# Power.net
KiCad netlist of a schematic drawn in Altium Designer
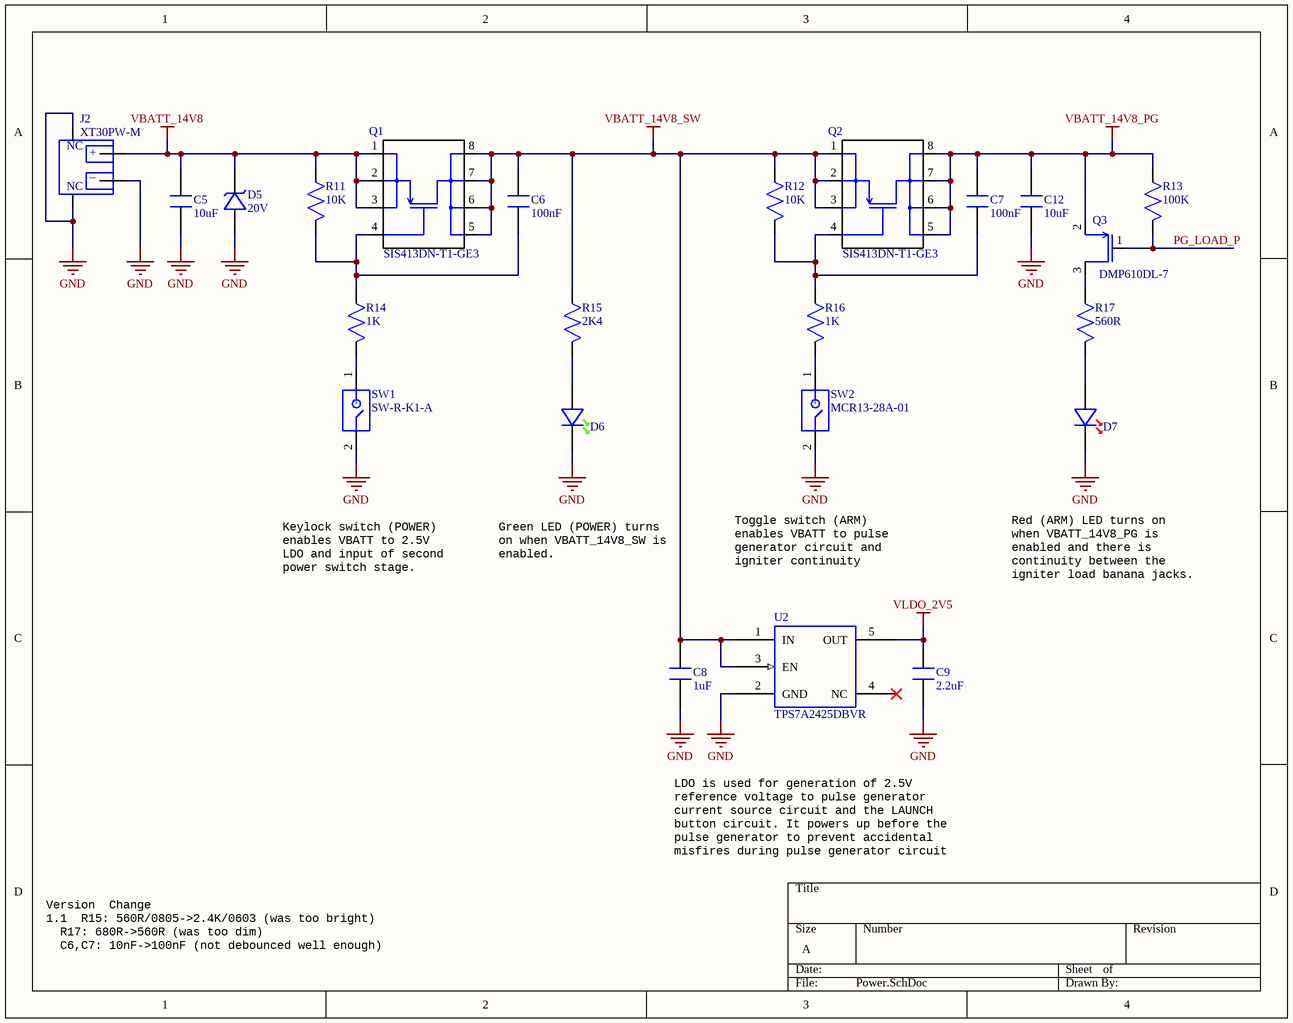
[diagram p0: Power.SchDoc]

(export (version "E")
  (design (tool "Eeschema 10.0.6"))
  (components
    (comp (ref "C5")
      (value "~")
      (footprint "1206_CAP")
      (fields
        (field (name "MANUFACTURER") "Samsung Electro-Mechanics")
        (field (name "PART NUMBER") "CL31A106MBHNNNE")
        (field (name "TOLERANCE") "20%")
        (field (name "CAPACITANCE") "10uF")
      )
      (libsource (lib "SharedPartsLib") (part "CAP_1206_10uF"))
    )
    (comp (ref "C6")
      (value "CAP_0603_100nF")
      (footprint "0603_CAP")
      (fields
        (field (name "MANUFACTURER") "Samsung Electro-Mechanics")
        (field (name "PART NUMBER") "CL10B104KB8NNWC")
        (field (name "TOLERANCE") "10%")
        (field (name "CAPACITANCE") "100nF")
      )
      (libsource (lib "SharedPartsLib") (part "CAP_0603_100nF"))
    )
    (comp (ref "C7")
      (value "CAP_0603_100nF")
      (footprint "0603_CAP")
      (fields
        (field (name "MANUFACTURER") "Samsung Electro-Mechanics")
        (field (name "PART NUMBER") "CL10B104KB8NNWC")
        (field (name "TOLERANCE") "10%")
        (field (name "CAPACITANCE") "100nF")
      )
      (libsource (lib "SharedPartsLib") (part "CAP_0603_100nF"))
    )
    (comp (ref "C8")
      (value "~")
      (footprint "0603_CAP")
      (fields
        (field (name "MANUFACTURER") "Samsung Electro-Mechanics")
        (field (name "PART NUMBER") "CL10B105KA8NNNC")
        (field (name "TOLERANCE") "10%")
        (field (name "CAPACITANCE") "1uF")
      )
      (libsource (lib "SharedPartsLib") (part "CAP_0603_1uF"))
    )
    (comp (ref "C9")
      (value "~")
      (footprint "0603_CAP")
      (fields
        (field (name "MANUFACTURER") "Samsung Electro-Mechanics")
        (field (name "PART NUMBER") "CL10B225KP8NNNC")
        (field (name "TOLERANCE") "10%")
        (field (name "CAPACITANCE") "2.2uF")
      )
      (libsource (lib "SharedPartsLib") (part "CAP_0603_2.2uF"))
    )
    (comp (ref "C12")
      (value "~")
      (footprint "1206_CAP")
      (fields
        (field (name "MANUFACTURER") "Samsung Electro-Mechanics")
        (field (name "PART NUMBER") "CL31A106MBHNNNE")
        (field (name "TOLERANCE") "20%")
        (field (name "CAPACITANCE") "10uF")
      )
      (libsource (lib "SharedPartsLib") (part "CAP_1206_10uF"))
    )
    (comp (ref "D5")
      (value "*")
      (footprint "DO-214AC_SMA")
      (fields
        (field (name "MANUFACTURER") "Diodes Incorporated")
        (field (name "PART NUMBER") "SMAJ20AQ-13-F")
        (field (name "REVERSE STANDOFF VOLTAGE") "20V")
      )
      (libsource (lib "SharedPartsLib") (part "DIODE_TVS_20V_UNIDIR"))
    )
    (comp (ref "D6")
      (value "*")
      (footprint "LED_1411")
      (fields (field (name "MANUFACTURER") "Würth Elektronik") (field (name "PART NUMBER") "150141GS73100"))
      (libsource (lib "SharedPartsLib") (part "LED_GREEN_150141GS73100"))
    )
    (comp (ref "D7")
      (value "*")
      (footprint "LED_1411")
      (fields (field (name "MANUFACTURER") "Würth Elektronik") (field (name "PART NUMBER") "150141RS73100"))
      (libsource (lib "SharedPartsLib") (part "LED_RED_150141RS73100"))
    )
    (comp (ref "J2")
      (value "~")
      (footprint "CONN_PLUG_XT30PW-M")
      (fields (field (name "MANUFACTURER") "AMASS") (field (name "PART NUMBER") "XT30PW-M"))
      (libsource (lib "SharedPartsLib") (part "CONN_PLUG_XT30PW-M"))
    )
    (comp (ref "Q1")
      (value "*")
      (footprint "PFET_POWERPAK_1212-8")
      (fields (field (name "MANUFACTURER") "Vishay Siliconix") (field (name "PART NUMBER") "SIS413DN-T1-GE3"))
      (libsource (lib "SharedPartsLib") (part "PFET_SIS413DN"))
    )
    (comp (ref "Q2")
      (value "*")
      (footprint "PFET_POWERPAK_1212-8")
      (fields (field (name "MANUFACTURER") "Vishay Siliconix") (field (name "PART NUMBER") "SIS413DN-T1-GE3"))
      (libsource (lib "SharedPartsLib") (part "PFET_SIS413DN"))
    )
    (comp (ref "Q3")
      (value "*")
      (footprint "SOT-23-3")
      (fields (field (name "MANUFACTURER") "Diodes Incorporated") (field (name "PART NUMBER") "DMP610DL-7"))
      (libsource (lib "SharedPartsLib") (part "PFET_DMP610DL"))
    )
    (comp (ref "R11")
      (value "~")
      (footprint "0603_RES")
      (fields
        (field (name "MANUFACTURER") "Stackpole Electronics Inc")
        (field (name "PART NUMBER") "RMCF0603FT10K0")
        (field (name "TOLERANCE") "1%")
        (field (name "RESISTANCE") "10K")
      )
      (libsource (lib "SharedPartsLib") (part "RES_0603_10K"))
    )
    (comp (ref "R12")
      (value "~")
      (footprint "0603_RES")
      (fields
        (field (name "MANUFACTURER") "Stackpole Electronics Inc")
        (field (name "PART NUMBER") "RMCF0603FT10K0")
        (field (name "TOLERANCE") "1%")
        (field (name "RESISTANCE") "10K")
      )
      (libsource (lib "SharedPartsLib") (part "RES_0603_10K"))
    )
    (comp (ref "R13")
      (value "~")
      (footprint "0603_RES")
      (fields
        (field (name "MANUFACTURER") "Stackpole")
        (field (name "PART NUMBER") "RMCF0603FT100K")
        (field (name "TOLERANCE") "1%")
        (field (name "RESISTANCE") "100K")
      )
      (libsource (lib "SharedPartsLib") (part "RES_0603_100K"))
    )
    (comp (ref "R14")
      (value "~")
      (footprint "0603_RES")
      (fields
        (field (name "MANUFACTURER") "Stackpole Electronics Inc")
        (field (name "PART NUMBER") "RMCF0603FT1K00")
        (field (name "TOLERANCE") "1%")
        (field (name "RESISTANCE") "1K")
      )
      (libsource (lib "SharedPartsLib") (part "RES_0603_1K"))
    )
    (comp (ref "R15")
      (value "RES_0603_2K4")
      (footprint "0603_RES")
      (fields
        (field (name "MANUFACTURER") "Stackpole Electronics Inc")
        (field (name "PART NUMBER") "RMCF0603FT2K40")
        (field (name "TOLERANCE") "1%")
        (field (name "RESISTANCE") "2K4")
      )
      (libsource (lib "SharedPartsLib") (part "RES_0603_2K4"))
    )
    (comp (ref "R16")
      (value "~")
      (footprint "0603_RES")
      (fields
        (field (name "MANUFACTURER") "Stackpole Electronics Inc")
        (field (name "PART NUMBER") "RMCF0603FT1K00")
        (field (name "TOLERANCE") "1%")
        (field (name "RESISTANCE") "1K")
      )
      (libsource (lib "SharedPartsLib") (part "RES_0603_1K"))
    )
    (comp (ref "R17")
      (value "RES_0805_560R")
      (footprint "0805_RES")
      (fields
        (field (name "MANUFACTURER") "Vishay Dale")
        (field (name "PART NUMBER") "CRCW0805560RFKEAHP")
        (field (name "TOLERANCE") "1%")
        (field (name "RESISTANCE") "560R")
      )
      (libsource (lib "SharedPartsLib") (part "RES_0805_560R"))
    )
    (comp (ref "SW1")
      (value "*")
      (footprint "SW_KEYLOCK_SW-R-K1-A")
      (fields (field (name "MANUFACTURER") "Adam Tech") (field (name "PART NUMBER") "SW-R-K1-A"))
      (libsource (lib "SharedPartsLib") (part "SW_KEYLOCK_SW-R-K1-A"))
    )
    (comp (ref "SW2")
      (value "*")
      (footprint "SW_TOGGLE_MCR13-28A-01")
      (fields (field (name "MANUFACTURER") "Multicomp") (field (name "PART NUMBER") "MCR13-28A-01"))
      (libsource (lib "SharedPartsLib") (part "SW_TOGGLE_MCR13-28A-01"))
    )
    (comp (ref "U2")
      (value "TPS7A2425DBVR")
      (footprint "SOT-23-5")
      (fields (field (name "MANUFACTURER") "Texas Instruments") (field (name "PART NUMBER") "TPS7A2425DBVR"))
      (libsource (lib "SharedPartsLib") (part "TPS7A2425DBVR"))
    )
  )
  (nets
    (net (code "1") (name "/PG_LOAD_P") (class "Default")
      (node (ref "Q3") (pin "1") (pinfunction "G_1") (pintype "passive"))
      (node (ref "R13") (pin "1") (pintype "passive"))
    )
    (net (code "2") (name "GND") (class "Default")
      (node (ref "C12") (pin "1") (pintype "passive"))
      (node (ref "C5") (pin "1") (pintype "passive"))
      (node (ref "C8") (pin "1") (pintype "passive"))
      (node (ref "C9") (pin "1") (pintype "passive"))
      (node (ref "D5") (pin "2") (pintype "passive"))
      (node (ref "D6") (pin "1") (pintype "passive"))
      (node (ref "D7") (pin "1") (pintype "passive"))
      (node (ref "J2") (pin "2") (pintype "passive"))
      (node (ref "SW1") (pin "2") (pintype "passive"))
      (node (ref "SW2") (pin "2") (pintype "passive"))
      (node (ref "U2") (pin "2") (pinfunction "GND_2") (pintype "passive"))
    )
    (net (code "3") (name "Net-(D6-Pad2)") (class "Default")
      (node (ref "D6") (pin "2") (pintype "passive"))
      (node (ref "R15") (pin "1") (pintype "passive"))
    )
    (net (code "4") (name "Net-(D7-Pad2)") (class "Default")
      (node (ref "D7") (pin "2") (pintype "passive"))
      (node (ref "R17") (pin "1") (pintype "passive"))
    )
    (net (code "5") (name "Net-(Q1-G)") (class "Default")
      (node (ref "C6") (pin "1") (pintype "passive"))
      (node (ref "Q1") (pin "4") (pinfunction "G_4") (pintype "passive"))
      (node (ref "R11") (pin "1") (pintype "passive"))
      (node (ref "R14") (pin "2") (pintype "passive"))
    )
    (net (code "6") (name "Net-(Q2-G)") (class "Default")
      (node (ref "C7") (pin "1") (pintype "passive"))
      (node (ref "Q2") (pin "4") (pinfunction "G_4") (pintype "passive"))
      (node (ref "R12") (pin "1") (pintype "passive"))
      (node (ref "R16") (pin "2") (pintype "passive"))
    )
    (net (code "7") (name "Net-(Q3-D)") (class "Default")
      (node (ref "Q3") (pin "3") (pinfunction "D_3") (pintype "passive"))
      (node (ref "R17") (pin "2") (pintype "passive"))
    )
    (net (code "8") (name "Net-(R14-Pad1)") (class "Default")
      (node (ref "R14") (pin "1") (pintype "passive"))
      (node (ref "SW1") (pin "1") (pintype "passive"))
    )
    (net (code "9") (name "Net-(R16-Pad1)") (class "Default")
      (node (ref "R16") (pin "1") (pintype "passive"))
      (node (ref "SW2") (pin "1") (pintype "passive"))
    )
    (net (code "10") (name "VBATT_14V8") (class "Default")
      (node (ref "C5") (pin "2") (pintype "passive"))
      (node (ref "D5") (pin "1") (pintype "passive"))
      (node (ref "J2") (pin "1") (pintype "passive"))
      (node (ref "Q1") (pin "1") (pinfunction "S_1") (pintype "passive"))
      (node (ref "Q1") (pin "2") (pinfunction "S_2") (pintype "passive"))
      (node (ref "Q1") (pin "3") (pinfunction "S_3") (pintype "passive"))
      (node (ref "R11") (pin "2") (pintype "passive"))
    )
    (net (code "11") (name "VBATT_14V8_PG") (class "Default")
      (node (ref "C12") (pin "2") (pintype "passive"))
      (node (ref "C7") (pin "2") (pintype "passive"))
      (node (ref "Q2") (pin "5") (pinfunction "D_5") (pintype "passive"))
      (node (ref "Q2") (pin "6") (pinfunction "D_6") (pintype "passive"))
      (node (ref "Q2") (pin "7") (pinfunction "D_7") (pintype "passive"))
      (node (ref "Q2") (pin "8") (pinfunction "D_8") (pintype "passive"))
      (node (ref "Q3") (pin "2") (pinfunction "S_2") (pintype "passive"))
      (node (ref "R13") (pin "2") (pintype "passive"))
    )
    (net (code "12") (name "VBATT_14V8_SW") (class "Default")
      (node (ref "C6") (pin "2") (pintype "passive"))
      (node (ref "C8") (pin "2") (pintype "passive"))
      (node (ref "Q1") (pin "5") (pinfunction "D_5") (pintype "passive"))
      (node (ref "Q1") (pin "6") (pinfunction "D_6") (pintype "passive"))
      (node (ref "Q1") (pin "7") (pinfunction "D_7") (pintype "passive"))
      (node (ref "Q1") (pin "8") (pinfunction "D_8") (pintype "passive"))
      (node (ref "Q2") (pin "1") (pinfunction "S_1") (pintype "passive"))
      (node (ref "Q2") (pin "2") (pinfunction "S_2") (pintype "passive"))
      (node (ref "Q2") (pin "3") (pinfunction "S_3") (pintype "passive"))
      (node (ref "R12") (pin "2") (pintype "passive"))
      (node (ref "R15") (pin "2") (pintype "passive"))
      (node (ref "U2") (pin "1") (pinfunction "IN_1") (pintype "passive"))
      (node (ref "U2") (pin "3") (pinfunction "EN_3") (pintype "input"))
    )
    (net (code "13") (name "VLDO_2V5") (class "Default")
      (node (ref "C9") (pin "2") (pintype "passive"))
      (node (ref "U2") (pin "5") (pinfunction "OUT_5") (pintype "passive"))
    )
    (net (code "14") (name "unconnected-(U2-NC-Pad4)") (class "Default")
      (node (ref "U2") (pin "4") (pinfunction "NC_4") (pintype "passive+no_connect"))
    )
  )
)
